# InputBoard_Analog_Digital.net
KiCad netlist of a schematic drawn in Altium Designer
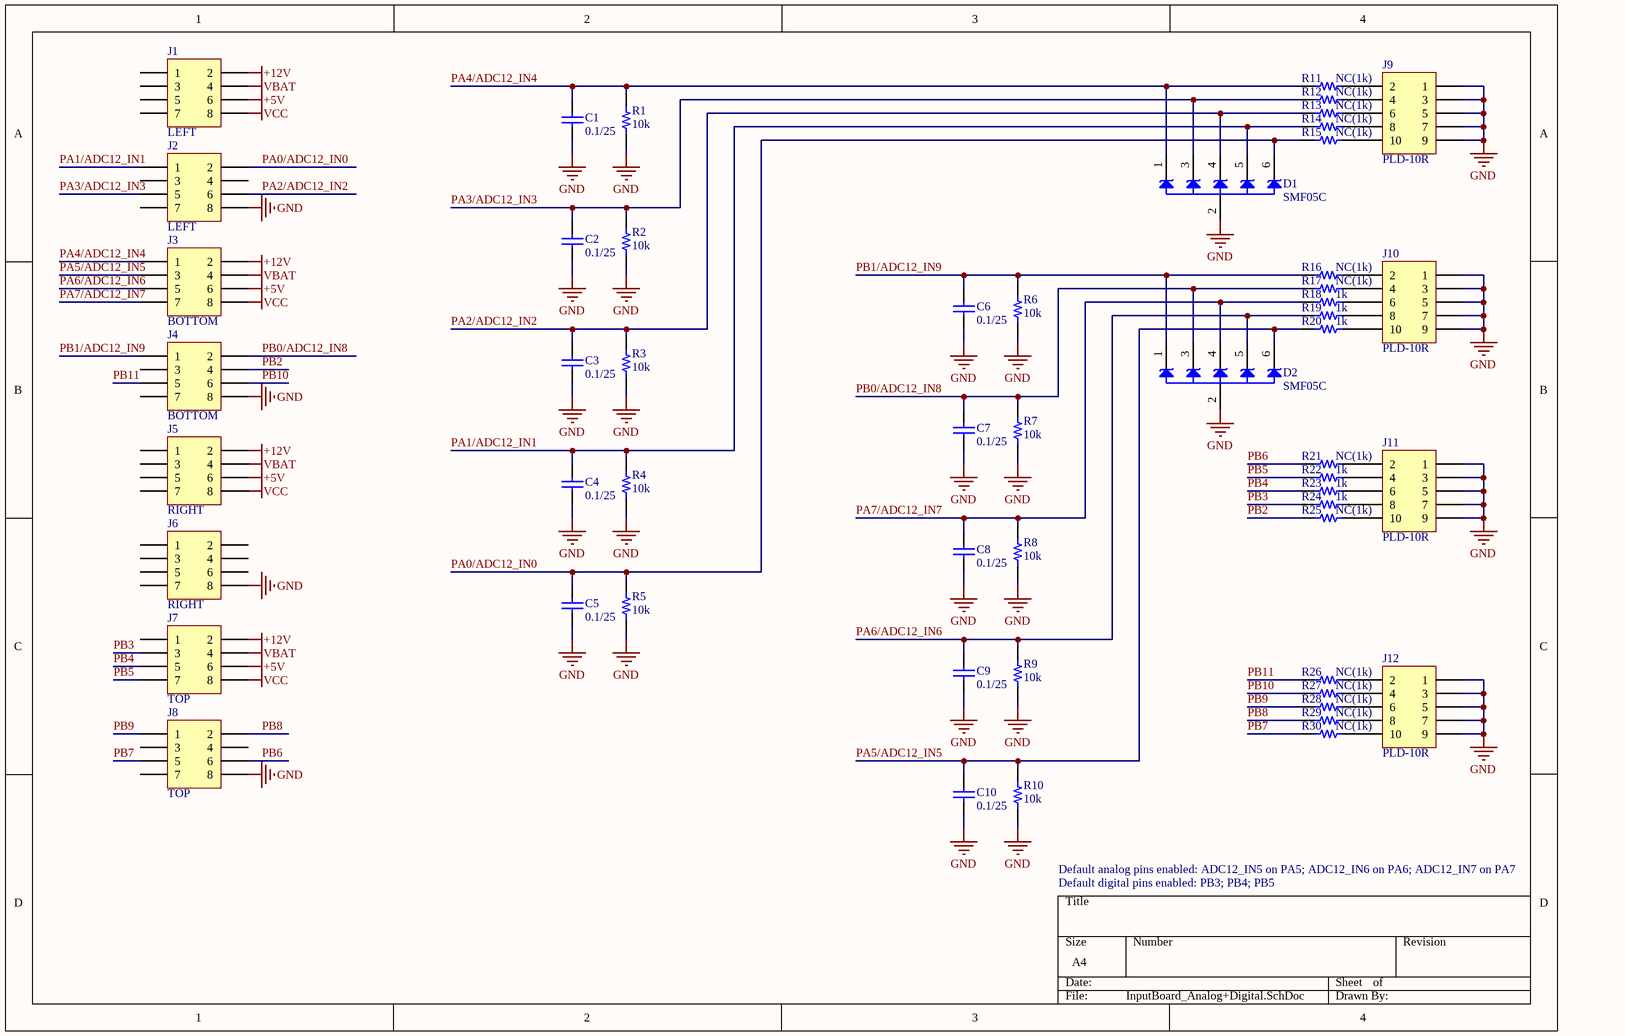
[diagram p0: InputBoard_Analog+Digital.SchDoc]

(export (version "E")
  (design (tool "Eeschema 10.0.6"))
  (components
    (comp (ref "C1")
      (value "0.1/25")
      (footprint "CAP0402")
      (description "Ceramic chip capacitor 0402")
      (fields
        (field (name "PARTNUMBER") "CAP0402")
        (field (name "VOLTAGE") "25")
        (field (name "AUTHOR") "oiezhov")
      )
      (libsource (lib "Library") (part "Capacitor"))
    )
    (comp (ref "C2")
      (value "0.1/25")
      (footprint "CAP0402")
      (description "Ceramic chip capacitor 0402")
      (fields
        (field (name "PARTNUMBER") "CAP0402")
        (field (name "VOLTAGE") "25")
        (field (name "AUTHOR") "oiezhov")
      )
      (libsource (lib "Library") (part "Capacitor"))
    )
    (comp (ref "C3")
      (value "0.1/25")
      (footprint "CAP0402")
      (description "Ceramic chip capacitor 0402")
      (fields
        (field (name "PARTNUMBER") "CAP0402")
        (field (name "VOLTAGE") "25")
        (field (name "AUTHOR") "oiezhov")
      )
      (libsource (lib "Library") (part "Capacitor"))
    )
    (comp (ref "C4")
      (value "0.1/25")
      (footprint "CAP0402")
      (description "Ceramic chip capacitor 0402")
      (fields
        (field (name "PARTNUMBER") "CAP0402")
        (field (name "VOLTAGE") "25")
        (field (name "AUTHOR") "oiezhov")
      )
      (libsource (lib "Library") (part "Capacitor"))
    )
    (comp (ref "C5")
      (value "0.1/25")
      (footprint "CAP0402")
      (description "Ceramic chip capacitor 0402")
      (fields
        (field (name "PARTNUMBER") "CAP0402")
        (field (name "VOLTAGE") "25")
        (field (name "AUTHOR") "oiezhov")
      )
      (libsource (lib "Library") (part "Capacitor"))
    )
    (comp (ref "C6")
      (value "0.1/25")
      (footprint "CAP0402")
      (description "Ceramic chip capacitor 0402")
      (fields
        (field (name "PARTNUMBER") "CAP0402")
        (field (name "VOLTAGE") "25")
        (field (name "AUTHOR") "oiezhov")
      )
      (libsource (lib "Library") (part "Capacitor"))
    )
    (comp (ref "C7")
      (value "0.1/25")
      (footprint "CAP0402")
      (description "Ceramic chip capacitor 0402")
      (fields
        (field (name "PARTNUMBER") "CAP0402")
        (field (name "VOLTAGE") "25")
        (field (name "AUTHOR") "oiezhov")
      )
      (libsource (lib "Library") (part "Capacitor"))
    )
    (comp (ref "C8")
      (value "0.1/25")
      (footprint "CAP0402")
      (description "Ceramic chip capacitor 0402")
      (fields
        (field (name "PARTNUMBER") "CAP0402")
        (field (name "VOLTAGE") "25")
        (field (name "AUTHOR") "oiezhov")
      )
      (libsource (lib "Library") (part "Capacitor"))
    )
    (comp (ref "C9")
      (value "0.1/25")
      (footprint "CAP0402")
      (description "Ceramic chip capacitor 0402")
      (fields
        (field (name "PARTNUMBER") "CAP0402")
        (field (name "VOLTAGE") "25")
        (field (name "AUTHOR") "oiezhov")
      )
      (libsource (lib "Library") (part "Capacitor"))
    )
    (comp (ref "C10")
      (value "0.1/25")
      (footprint "CAP0402")
      (description "Ceramic chip capacitor 0402")
      (fields
        (field (name "PARTNUMBER") "CAP0402")
        (field (name "VOLTAGE") "25")
        (field (name "AUTHOR") "oiezhov")
      )
      (libsource (lib "Library") (part "Capacitor"))
    )
    (comp (ref "D1")
      (value "SMF05C")
      (footprint "SOT363")
      (description "5-line TVS Array for ESD and Latch-Up Protection")
      (fields (field (name "AUTHOR") "oiezhov"))
      (libsource (lib "Library") (part "5x TVS array"))
    )
    (comp (ref "D2")
      (value "SMF05C")
      (footprint "SOT363")
      (description "5-line TVS Array for ESD and Latch-Up Protection")
      (fields (field (name "AUTHOR") "oiezhov"))
      (libsource (lib "Library") (part "5x TVS array"))
    )
    (comp (ref "J1")
      (value "LEFT")
      (footprint "PBDM-8")
      (description "2x4-pin header, pitch 2.54 mm")
      (fields (field (name "PARTNUMBER") "PBDM-8") (field (name "AUTHOR") "oiezhov"))
      (libsource (lib "Library") (part "8-pin dual row connector"))
    )
    (comp (ref "J2")
      (value "LEFT")
      (footprint "PBDM-8")
      (description "2x4-pin header, pitch 2.54 mm")
      (fields (field (name "PARTNUMBER") "PBDM-8") (field (name "AUTHOR") "oiezhov"))
      (libsource (lib "Library") (part "8-pin dual row connector"))
    )
    (comp (ref "J3")
      (value "BOTTOM")
      (footprint "PBDM-8")
      (description "2x4-pin header, pitch 2.54 mm")
      (fields (field (name "PARTNUMBER") "PBDM-8") (field (name "AUTHOR") "oiezhov"))
      (libsource (lib "Library") (part "8-pin dual row connector"))
    )
    (comp (ref "J4")
      (value "BOTTOM")
      (footprint "PBDM-8")
      (description "2x4-pin header, pitch 2.54 mm")
      (fields (field (name "PARTNUMBER") "PBDM-8") (field (name "AUTHOR") "oiezhov"))
      (libsource (lib "Library") (part "8-pin dual row connector"))
    )
    (comp (ref "J5")
      (value "RIGHT")
      (footprint "PBDM-8")
      (description "2x4-pin header, pitch 2.54 mm")
      (fields (field (name "PARTNUMBER") "PBDM-8") (field (name "AUTHOR") "oiezhov"))
      (libsource (lib "Library") (part "8-pin dual row connector"))
    )
    (comp (ref "J6")
      (value "RIGHT")
      (footprint "PBDM-8")
      (description "2x4-pin header, pitch 2.54 mm")
      (fields (field (name "PARTNUMBER") "PBDM-8") (field (name "AUTHOR") "oiezhov"))
      (libsource (lib "Library") (part "8-pin dual row connector"))
    )
    (comp (ref "J7")
      (value "TOP")
      (footprint "PBDM-8")
      (description "2x4-pin header, pitch 2.54 mm")
      (fields (field (name "PARTNUMBER") "PBDM-8") (field (name "AUTHOR") "oiezhov"))
      (libsource (lib "Library") (part "8-pin dual row connector"))
    )
    (comp (ref "J8")
      (value "TOP")
      (footprint "PBDM-8")
      (description "2x4-pin header, pitch 2.54 mm")
      (fields (field (name "PARTNUMBER") "PBDM-8") (field (name "AUTHOR") "oiezhov"))
      (libsource (lib "Library") (part "8-pin dual row connector"))
    )
    (comp (ref "J9")
      (value "PLD-10R")
      (footprint "PLD-10R")
      (description "2x5-pin angle header, pitch 2.54 mm")
      (fields (field (name "AUTHOR") "oiezhov"))
      (libsource (lib "Library") (part "10-pin dual row connector"))
    )
    (comp (ref "J10")
      (value "PLD-10R")
      (footprint "PLD-10R")
      (description "2x5-pin angle header, pitch 2.54 mm")
      (fields (field (name "AUTHOR") "oiezhov"))
      (libsource (lib "Library") (part "10-pin dual row connector"))
    )
    (comp (ref "J11")
      (value "PLD-10R")
      (footprint "PLD-10R")
      (description "2x5-pin angle header, pitch 2.54 mm")
      (fields (field (name "AUTHOR") "oiezhov"))
      (libsource (lib "Library") (part "10-pin dual row connector"))
    )
    (comp (ref "J12")
      (value "PLD-10R")
      (footprint "PLD-10R")
      (description "2x5-pin angle header, pitch 2.54 mm")
      (fields (field (name "AUTHOR") "oiezhov"))
      (libsource (lib "Library") (part "10-pin dual row connector"))
    )
    (comp (ref "R1")
      (value "10k")
      (footprint "RES0402")
      (description "Ceramic chip resistor")
      (fields (field (name "PARTNUMBER") "RES0402") (field (name "AUTHOR") "oiezhov"))
      (libsource (lib "Library") (part "Resistor"))
    )
    (comp (ref "R2")
      (value "10k")
      (footprint "RES0402")
      (description "Ceramic chip resistor")
      (fields (field (name "PARTNUMBER") "RES0402") (field (name "AUTHOR") "oiezhov"))
      (libsource (lib "Library") (part "Resistor"))
    )
    (comp (ref "R3")
      (value "10k")
      (footprint "RES0402")
      (description "Ceramic chip resistor")
      (fields (field (name "PARTNUMBER") "RES0402") (field (name "AUTHOR") "oiezhov"))
      (libsource (lib "Library") (part "Resistor"))
    )
    (comp (ref "R4")
      (value "10k")
      (footprint "RES0402")
      (description "Ceramic chip resistor")
      (fields (field (name "PARTNUMBER") "RES0402") (field (name "AUTHOR") "oiezhov"))
      (libsource (lib "Library") (part "Resistor"))
    )
    (comp (ref "R5")
      (value "10k")
      (footprint "RES0402")
      (description "Ceramic chip resistor")
      (fields (field (name "PARTNUMBER") "RES0402") (field (name "AUTHOR") "oiezhov"))
      (libsource (lib "Library") (part "Resistor"))
    )
    (comp (ref "R6")
      (value "10k")
      (footprint "RES0402")
      (description "Ceramic chip resistor")
      (fields (field (name "PARTNUMBER") "RES0402") (field (name "AUTHOR") "oiezhov"))
      (libsource (lib "Library") (part "Resistor"))
    )
    (comp (ref "R7")
      (value "10k")
      (footprint "RES0402")
      (description "Ceramic chip resistor")
      (fields (field (name "PARTNUMBER") "RES0402") (field (name "AUTHOR") "oiezhov"))
      (libsource (lib "Library") (part "Resistor"))
    )
    (comp (ref "R8")
      (value "10k")
      (footprint "RES0402")
      (description "Ceramic chip resistor")
      (fields (field (name "PARTNUMBER") "RES0402") (field (name "AUTHOR") "oiezhov"))
      (libsource (lib "Library") (part "Resistor"))
    )
    (comp (ref "R9")
      (value "10k")
      (footprint "RES0402")
      (description "Ceramic chip resistor")
      (fields (field (name "PARTNUMBER") "RES0402") (field (name "AUTHOR") "oiezhov"))
      (libsource (lib "Library") (part "Resistor"))
    )
    (comp (ref "R10")
      (value "10k")
      (footprint "RES0402")
      (description "Ceramic chip resistor")
      (fields (field (name "PARTNUMBER") "RES0402") (field (name "AUTHOR") "oiezhov"))
      (libsource (lib "Library") (part "Resistor"))
    )
    (comp (ref "R11")
      (value "NC(1k)")
      (footprint "RES0402")
      (description "Ceramic chip resistor")
      (fields (field (name "PARTNUMBER") "RES0402") (field (name "AUTHOR") "oiezhov"))
      (libsource (lib "Library") (part "Resistor"))
    )
    (comp (ref "R12")
      (value "NC(1k)")
      (footprint "RES0402")
      (description "Ceramic chip resistor")
      (fields (field (name "PARTNUMBER") "RES0402") (field (name "AUTHOR") "oiezhov"))
      (libsource (lib "Library") (part "Resistor"))
    )
    (comp (ref "R13")
      (value "NC(1k)")
      (footprint "RES0402")
      (description "Ceramic chip resistor")
      (fields (field (name "PARTNUMBER") "RES0402") (field (name "AUTHOR") "oiezhov"))
      (libsource (lib "Library") (part "Resistor"))
    )
    (comp (ref "R14")
      (value "NC(1k)")
      (footprint "RES0402")
      (description "Ceramic chip resistor")
      (fields (field (name "PARTNUMBER") "RES0402") (field (name "AUTHOR") "oiezhov"))
      (libsource (lib "Library") (part "Resistor"))
    )
    (comp (ref "R15")
      (value "NC(1k)")
      (footprint "RES0402")
      (description "Ceramic chip resistor")
      (fields (field (name "PARTNUMBER") "RES0402") (field (name "AUTHOR") "oiezhov"))
      (libsource (lib "Library") (part "Resistor"))
    )
    (comp (ref "R16")
      (value "NC(1k)")
      (footprint "RES0402")
      (description "Ceramic chip resistor")
      (fields (field (name "PARTNUMBER") "RES0402") (field (name "AUTHOR") "oiezhov"))
      (libsource (lib "Library") (part "Resistor"))
    )
    (comp (ref "R17")
      (value "NC(1k)")
      (footprint "RES0402")
      (description "Ceramic chip resistor")
      (fields (field (name "PARTNUMBER") "RES0402") (field (name "AUTHOR") "oiezhov"))
      (libsource (lib "Library") (part "Resistor"))
    )
    (comp (ref "R18")
      (value "1k")
      (footprint "RES0402")
      (description "Ceramic chip resistor")
      (fields (field (name "PARTNUMBER") "RES0402") (field (name "AUTHOR") "oiezhov"))
      (libsource (lib "Library") (part "Resistor"))
    )
    (comp (ref "R19")
      (value "1k")
      (footprint "RES0402")
      (description "Ceramic chip resistor")
      (fields (field (name "PARTNUMBER") "RES0402") (field (name "AUTHOR") "oiezhov"))
      (libsource (lib "Library") (part "Resistor"))
    )
    (comp (ref "R20")
      (value "1k")
      (footprint "RES0402")
      (description "Ceramic chip resistor")
      (fields (field (name "PARTNUMBER") "RES0402") (field (name "AUTHOR") "oiezhov"))
      (libsource (lib "Library") (part "Resistor"))
    )
    (comp (ref "R21")
      (value "NC(1k)")
      (footprint "RES0402")
      (description "Ceramic chip resistor")
      (fields (field (name "PARTNUMBER") "RES0402") (field (name "AUTHOR") "oiezhov"))
      (libsource (lib "Library") (part "Resistor"))
    )
    (comp (ref "R22")
      (value "1k")
      (footprint "RES0402")
      (description "Ceramic chip resistor")
      (fields (field (name "PARTNUMBER") "RES0402") (field (name "AUTHOR") "oiezhov"))
      (libsource (lib "Library") (part "Resistor"))
    )
    (comp (ref "R23")
      (value "1k")
      (footprint "RES0402")
      (description "Ceramic chip resistor")
      (fields (field (name "PARTNUMBER") "RES0402") (field (name "AUTHOR") "oiezhov"))
      (libsource (lib "Library") (part "Resistor"))
    )
    (comp (ref "R24")
      (value "1k")
      (footprint "RES0402")
      (description "Ceramic chip resistor")
      (fields (field (name "PARTNUMBER") "RES0402") (field (name "AUTHOR") "oiezhov"))
      (libsource (lib "Library") (part "Resistor"))
    )
    (comp (ref "R25")
      (value "NC(1k)")
      (footprint "RES0402")
      (description "Ceramic chip resistor")
      (fields (field (name "PARTNUMBER") "RES0402") (field (name "AUTHOR") "oiezhov"))
      (libsource (lib "Library") (part "Resistor"))
    )
    (comp (ref "R26")
      (value "NC(1k)")
      (footprint "RES0402")
      (description "Ceramic chip resistor")
      (fields (field (name "PARTNUMBER") "RES0402") (field (name "AUTHOR") "oiezhov"))
      (libsource (lib "Library") (part "Resistor"))
    )
    (comp (ref "R27")
      (value "NC(1k)")
      (footprint "RES0402")
      (description "Ceramic chip resistor")
      (fields (field (name "PARTNUMBER") "RES0402") (field (name "AUTHOR") "oiezhov"))
      (libsource (lib "Library") (part "Resistor"))
    )
    (comp (ref "R28")
      (value "NC(1k)")
      (footprint "RES0402")
      (description "Ceramic chip resistor")
      (fields (field (name "PARTNUMBER") "RES0402") (field (name "AUTHOR") "oiezhov"))
      (libsource (lib "Library") (part "Resistor"))
    )
    (comp (ref "R29")
      (value "NC(1k)")
      (footprint "RES0402")
      (description "Ceramic chip resistor")
      (fields (field (name "PARTNUMBER") "RES0402") (field (name "AUTHOR") "oiezhov"))
      (libsource (lib "Library") (part "Resistor"))
    )
    (comp (ref "R30")
      (value "NC(1k)")
      (footprint "RES0402")
      (description "Ceramic chip resistor")
      (fields (field (name "PARTNUMBER") "RES0402") (field (name "AUTHOR") "oiezhov"))
      (libsource (lib "Library") (part "Resistor"))
    )
  )
  (nets
    (net (code "1") (name "+5V") (class "Default")
      (node (ref "J1") (pin "6") (pinfunction "6_6") (pintype "passive"))
      (node (ref "J3") (pin "6") (pinfunction "6_6") (pintype "passive"))
      (node (ref "J5") (pin "6") (pinfunction "6_6") (pintype "passive"))
      (node (ref "J7") (pin "6") (pinfunction "6_6") (pintype "passive"))
    )
    (net (code "2") (name "+12V") (class "Default")
      (node (ref "J1") (pin "2") (pinfunction "2_2") (pintype "passive"))
      (node (ref "J3") (pin "2") (pinfunction "2_2") (pintype "passive"))
      (node (ref "J5") (pin "2") (pinfunction "2_2") (pintype "passive"))
      (node (ref "J7") (pin "2") (pinfunction "2_2") (pintype "passive"))
    )
    (net (code "3") (name "/PA0{slash}ADC12_IN0") (class "Default")
      (node (ref "C5") (pin "2") (pinfunction "2_2") (pintype "passive"))
      (node (ref "D1") (pin "6") (pinfunction "6_6") (pintype "passive"))
      (node (ref "J2") (pin "2") (pinfunction "2_2") (pintype "passive"))
      (node (ref "R15") (pin "1") (pinfunction "1_1") (pintype "passive"))
      (node (ref "R5") (pin "1") (pinfunction "1_1") (pintype "passive"))
    )
    (net (code "4") (name "/PA1{slash}ADC12_IN1") (class "Default")
      (node (ref "C4") (pin "2") (pinfunction "2_2") (pintype "passive"))
      (node (ref "D1") (pin "5") (pinfunction "5_5") (pintype "passive"))
      (node (ref "J2") (pin "1") (pinfunction "1_1") (pintype "passive"))
      (node (ref "R14") (pin "1") (pinfunction "1_1") (pintype "passive"))
      (node (ref "R4") (pin "1") (pinfunction "1_1") (pintype "passive"))
    )
    (net (code "5") (name "/PA2{slash}ADC12_IN2") (class "Default")
      (node (ref "C3") (pin "2") (pinfunction "2_2") (pintype "passive"))
      (node (ref "D1") (pin "4") (pinfunction "4_4") (pintype "passive"))
      (node (ref "J2") (pin "6") (pinfunction "6_6") (pintype "passive"))
      (node (ref "R13") (pin "1") (pinfunction "1_1") (pintype "passive"))
      (node (ref "R3") (pin "1") (pinfunction "1_1") (pintype "passive"))
    )
    (net (code "6") (name "/PA3{slash}ADC12_IN3") (class "Default")
      (node (ref "C2") (pin "2") (pinfunction "2_2") (pintype "passive"))
      (node (ref "D1") (pin "3") (pinfunction "3_3") (pintype "passive"))
      (node (ref "J2") (pin "5") (pinfunction "5_5") (pintype "passive"))
      (node (ref "R12") (pin "1") (pinfunction "1_1") (pintype "passive"))
      (node (ref "R2") (pin "1") (pinfunction "1_1") (pintype "passive"))
    )
    (net (code "7") (name "/PA4{slash}ADC12_IN4") (class "Default")
      (node (ref "C1") (pin "2") (pinfunction "2_2") (pintype "passive"))
      (node (ref "D1") (pin "1") (pinfunction "1_1") (pintype "passive"))
      (node (ref "J3") (pin "1") (pinfunction "1_1") (pintype "passive"))
      (node (ref "R1") (pin "1") (pinfunction "1_1") (pintype "passive"))
      (node (ref "R11") (pin "1") (pinfunction "1_1") (pintype "passive"))
    )
    (net (code "8") (name "/PA5{slash}ADC12_IN5") (class "Default")
      (node (ref "C10") (pin "2") (pinfunction "2_2") (pintype "passive"))
      (node (ref "D2") (pin "6") (pinfunction "6_6") (pintype "passive"))
      (node (ref "J3") (pin "3") (pinfunction "3_3") (pintype "passive"))
      (node (ref "R10") (pin "1") (pinfunction "1_1") (pintype "passive"))
      (node (ref "R20") (pin "1") (pinfunction "1_1") (pintype "passive"))
    )
    (net (code "9") (name "/PA6{slash}ADC12_IN6") (class "Default")
      (node (ref "C9") (pin "2") (pinfunction "2_2") (pintype "passive"))
      (node (ref "D2") (pin "5") (pinfunction "5_5") (pintype "passive"))
      (node (ref "J3") (pin "5") (pinfunction "5_5") (pintype "passive"))
      (node (ref "R19") (pin "1") (pinfunction "1_1") (pintype "passive"))
      (node (ref "R9") (pin "1") (pinfunction "1_1") (pintype "passive"))
    )
    (net (code "10") (name "/PA7{slash}ADC12_IN7") (class "Default")
      (node (ref "C8") (pin "2") (pinfunction "2_2") (pintype "passive"))
      (node (ref "D2") (pin "4") (pinfunction "4_4") (pintype "passive"))
      (node (ref "J3") (pin "7") (pinfunction "7_7") (pintype "passive"))
      (node (ref "R18") (pin "1") (pinfunction "1_1") (pintype "passive"))
      (node (ref "R8") (pin "1") (pinfunction "1_1") (pintype "passive"))
    )
    (net (code "11") (name "/PB0{slash}ADC12_IN8") (class "Default")
      (node (ref "C7") (pin "2") (pinfunction "2_2") (pintype "passive"))
      (node (ref "D2") (pin "3") (pinfunction "3_3") (pintype "passive"))
      (node (ref "J4") (pin "2") (pinfunction "2_2") (pintype "passive"))
      (node (ref "R17") (pin "1") (pinfunction "1_1") (pintype "passive"))
      (node (ref "R7") (pin "1") (pinfunction "1_1") (pintype "passive"))
    )
    (net (code "12") (name "/PB1{slash}ADC12_IN9") (class "Default")
      (node (ref "C6") (pin "2") (pinfunction "2_2") (pintype "passive"))
      (node (ref "D2") (pin "1") (pinfunction "1_1") (pintype "passive"))
      (node (ref "J4") (pin "1") (pinfunction "1_1") (pintype "passive"))
      (node (ref "R16") (pin "1") (pinfunction "1_1") (pintype "passive"))
      (node (ref "R6") (pin "1") (pinfunction "1_1") (pintype "passive"))
    )
    (net (code "13") (name "/PB2") (class "Default")
      (node (ref "J4") (pin "4") (pinfunction "4_4") (pintype "passive"))
      (node (ref "R25") (pin "1") (pinfunction "1_1") (pintype "passive"))
    )
    (net (code "14") (name "/PB3") (class "Default")
      (node (ref "J7") (pin "3") (pinfunction "3_3") (pintype "passive"))
      (node (ref "R24") (pin "1") (pinfunction "1_1") (pintype "passive"))
    )
    (net (code "15") (name "/PB4") (class "Default")
      (node (ref "J7") (pin "5") (pinfunction "5_5") (pintype "passive"))
      (node (ref "R23") (pin "1") (pinfunction "1_1") (pintype "passive"))
    )
    (net (code "16") (name "/PB5") (class "Default")
      (node (ref "J7") (pin "7") (pinfunction "7_7") (pintype "passive"))
      (node (ref "R22") (pin "1") (pinfunction "1_1") (pintype "passive"))
    )
    (net (code "17") (name "/PB6") (class "Default")
      (node (ref "J8") (pin "6") (pinfunction "6_6") (pintype "passive"))
      (node (ref "R21") (pin "1") (pinfunction "1_1") (pintype "passive"))
    )
    (net (code "18") (name "/PB7") (class "Default")
      (node (ref "J8") (pin "5") (pinfunction "5_5") (pintype "passive"))
      (node (ref "R30") (pin "1") (pinfunction "1_1") (pintype "passive"))
    )
    (net (code "19") (name "/PB8") (class "Default")
      (node (ref "J8") (pin "2") (pinfunction "2_2") (pintype "passive"))
      (node (ref "R29") (pin "1") (pinfunction "1_1") (pintype "passive"))
    )
    (net (code "20") (name "/PB9") (class "Default")
      (node (ref "J8") (pin "1") (pinfunction "1_1") (pintype "passive"))
      (node (ref "R28") (pin "1") (pinfunction "1_1") (pintype "passive"))
    )
    (net (code "21") (name "/PB10") (class "Default")
      (node (ref "J4") (pin "6") (pinfunction "6_6") (pintype "passive"))
      (node (ref "R27") (pin "1") (pinfunction "1_1") (pintype "passive"))
    )
    (net (code "22") (name "/PB11") (class "Default")
      (node (ref "J4") (pin "5") (pinfunction "5_5") (pintype "passive"))
      (node (ref "R26") (pin "1") (pinfunction "1_1") (pintype "passive"))
    )
    (net (code "23") (name "GND") (class "Default")
      (node (ref "C1") (pin "1") (pinfunction "1_1") (pintype "passive"))
      (node (ref "C10") (pin "1") (pinfunction "1_1") (pintype "passive"))
      (node (ref "C2") (pin "1") (pinfunction "1_1") (pintype "passive"))
      (node (ref "C3") (pin "1") (pinfunction "1_1") (pintype "passive"))
      (node (ref "C4") (pin "1") (pinfunction "1_1") (pintype "passive"))
      (node (ref "C5") (pin "1") (pinfunction "1_1") (pintype "passive"))
      (node (ref "C6") (pin "1") (pinfunction "1_1") (pintype "passive"))
      (node (ref "C7") (pin "1") (pinfunction "1_1") (pintype "passive"))
      (node (ref "C8") (pin "1") (pinfunction "1_1") (pintype "passive"))
      (node (ref "C9") (pin "1") (pinfunction "1_1") (pintype "passive"))
      (node (ref "D1") (pin "2") (pinfunction "2_2") (pintype "passive"))
      (node (ref "D2") (pin "2") (pinfunction "2_2") (pintype "passive"))
      (node (ref "J10") (pin "1") (pinfunction "1_1") (pintype "passive"))
      (node (ref "J10") (pin "3") (pinfunction "3_3") (pintype "passive"))
      (node (ref "J10") (pin "5") (pinfunction "5_5") (pintype "passive"))
      (node (ref "J10") (pin "7") (pinfunction "7_7") (pintype "passive"))
      (node (ref "J10") (pin "9") (pinfunction "9_9") (pintype "passive"))
      (node (ref "J11") (pin "1") (pinfunction "1_1") (pintype "passive"))
      (node (ref "J11") (pin "3") (pinfunction "3_3") (pintype "passive"))
      (node (ref "J11") (pin "5") (pinfunction "5_5") (pintype "passive"))
      (node (ref "J11") (pin "7") (pinfunction "7_7") (pintype "passive"))
      (node (ref "J11") (pin "9") (pinfunction "9_9") (pintype "passive"))
      (node (ref "J12") (pin "1") (pinfunction "1_1") (pintype "passive"))
      (node (ref "J12") (pin "3") (pinfunction "3_3") (pintype "passive"))
      (node (ref "J12") (pin "5") (pinfunction "5_5") (pintype "passive"))
      (node (ref "J12") (pin "7") (pinfunction "7_7") (pintype "passive"))
      (node (ref "J12") (pin "9") (pinfunction "9_9") (pintype "passive"))
      (node (ref "J2") (pin "8") (pinfunction "8_8") (pintype "passive"))
      (node (ref "J4") (pin "8") (pinfunction "8_8") (pintype "passive"))
      (node (ref "J6") (pin "8") (pinfunction "8_8") (pintype "passive"))
      (node (ref "J8") (pin "8") (pinfunction "8_8") (pintype "passive"))
      (node (ref "J9") (pin "1") (pinfunction "1_1") (pintype "passive"))
      (node (ref "J9") (pin "3") (pinfunction "3_3") (pintype "passive"))
      (node (ref "J9") (pin "5") (pinfunction "5_5") (pintype "passive"))
      (node (ref "J9") (pin "7") (pinfunction "7_7") (pintype "passive"))
      (node (ref "J9") (pin "9") (pinfunction "9_9") (pintype "passive"))
      (node (ref "R1") (pin "2") (pinfunction "2_2") (pintype "passive"))
      (node (ref "R10") (pin "2") (pinfunction "2_2") (pintype "passive"))
      (node (ref "R2") (pin "2") (pinfunction "2_2") (pintype "passive"))
      (node (ref "R3") (pin "2") (pinfunction "2_2") (pintype "passive"))
      (node (ref "R4") (pin "2") (pinfunction "2_2") (pintype "passive"))
      (node (ref "R5") (pin "2") (pinfunction "2_2") (pintype "passive"))
      (node (ref "R6") (pin "2") (pinfunction "2_2") (pintype "passive"))
      (node (ref "R7") (pin "2") (pinfunction "2_2") (pintype "passive"))
      (node (ref "R8") (pin "2") (pinfunction "2_2") (pintype "passive"))
      (node (ref "R9") (pin "2") (pinfunction "2_2") (pintype "passive"))
    )
    (net (code "24") (name "Net-(J9-Pad2)") (class "Default")
      (node (ref "J9") (pin "2") (pinfunction "2_2") (pintype "passive"))
      (node (ref "R11") (pin "2") (pinfunction "2_2") (pintype "passive"))
    )
    (net (code "25") (name "Net-(J9-Pad4)") (class "Default")
      (node (ref "J9") (pin "4") (pinfunction "4_4") (pintype "passive"))
      (node (ref "R12") (pin "2") (pinfunction "2_2") (pintype "passive"))
    )
    (net (code "26") (name "Net-(J9-Pad6)") (class "Default")
      (node (ref "J9") (pin "6") (pinfunction "6_6") (pintype "passive"))
      (node (ref "R13") (pin "2") (pinfunction "2_2") (pintype "passive"))
    )
    (net (code "27") (name "Net-(J9-Pad8)") (class "Default")
      (node (ref "J9") (pin "8") (pinfunction "8_8") (pintype "passive"))
      (node (ref "R14") (pin "2") (pinfunction "2_2") (pintype "passive"))
    )
    (net (code "28") (name "Net-(J9-Pad10)") (class "Default")
      (node (ref "J9") (pin "10") (pinfunction "10_10") (pintype "passive"))
      (node (ref "R15") (pin "2") (pinfunction "2_2") (pintype "passive"))
    )
    (net (code "29") (name "Net-(J10-Pad2)") (class "Default")
      (node (ref "J10") (pin "2") (pinfunction "2_2") (pintype "passive"))
      (node (ref "R16") (pin "2") (pinfunction "2_2") (pintype "passive"))
    )
    (net (code "30") (name "Net-(J10-Pad4)") (class "Default")
      (node (ref "J10") (pin "4") (pinfunction "4_4") (pintype "passive"))
      (node (ref "R17") (pin "2") (pinfunction "2_2") (pintype "passive"))
    )
    (net (code "31") (name "Net-(J10-Pad6)") (class "Default")
      (node (ref "J10") (pin "6") (pinfunction "6_6") (pintype "passive"))
      (node (ref "R18") (pin "2") (pinfunction "2_2") (pintype "passive"))
    )
    (net (code "32") (name "Net-(J10-Pad8)") (class "Default")
      (node (ref "J10") (pin "8") (pinfunction "8_8") (pintype "passive"))
      (node (ref "R19") (pin "2") (pinfunction "2_2") (pintype "passive"))
    )
    (net (code "33") (name "Net-(J10-Pad10)") (class "Default")
      (node (ref "J10") (pin "10") (pinfunction "10_10") (pintype "passive"))
      (node (ref "R20") (pin "2") (pinfunction "2_2") (pintype "passive"))
    )
    (net (code "34") (name "Net-(J11-Pad2)") (class "Default")
      (node (ref "J11") (pin "2") (pinfunction "2_2") (pintype "passive"))
      (node (ref "R21") (pin "2") (pinfunction "2_2") (pintype "passive"))
    )
    (net (code "35") (name "Net-(J11-Pad4)") (class "Default")
      (node (ref "J11") (pin "4") (pinfunction "4_4") (pintype "passive"))
      (node (ref "R22") (pin "2") (pinfunction "2_2") (pintype "passive"))
    )
    (net (code "36") (name "Net-(J11-Pad6)") (class "Default")
      (node (ref "J11") (pin "6") (pinfunction "6_6") (pintype "passive"))
      (node (ref "R23") (pin "2") (pinfunction "2_2") (pintype "passive"))
    )
    (net (code "37") (name "Net-(J11-Pad8)") (class "Default")
      (node (ref "J11") (pin "8") (pinfunction "8_8") (pintype "passive"))
      (node (ref "R24") (pin "2") (pinfunction "2_2") (pintype "passive"))
    )
    (net (code "38") (name "Net-(J11-Pad10)") (class "Default")
      (node (ref "J11") (pin "10") (pinfunction "10_10") (pintype "passive"))
      (node (ref "R25") (pin "2") (pinfunction "2_2") (pintype "passive"))
    )
    (net (code "39") (name "Net-(J12-Pad2)") (class "Default")
      (node (ref "J12") (pin "2") (pinfunction "2_2") (pintype "passive"))
      (node (ref "R26") (pin "2") (pinfunction "2_2") (pintype "passive"))
    )
    (net (code "40") (name "Net-(J12-Pad4)") (class "Default")
      (node (ref "J12") (pin "4") (pinfunction "4_4") (pintype "passive"))
      (node (ref "R27") (pin "2") (pinfunction "2_2") (pintype "passive"))
    )
    (net (code "41") (name "Net-(J12-Pad6)") (class "Default")
      (node (ref "J12") (pin "6") (pinfunction "6_6") (pintype "passive"))
      (node (ref "R28") (pin "2") (pinfunction "2_2") (pintype "passive"))
    )
    (net (code "42") (name "Net-(J12-Pad8)") (class "Default")
      (node (ref "J12") (pin "8") (pinfunction "8_8") (pintype "passive"))
      (node (ref "R29") (pin "2") (pinfunction "2_2") (pintype "passive"))
    )
    (net (code "43") (name "Net-(J12-Pad10)") (class "Default")
      (node (ref "J12") (pin "10") (pinfunction "10_10") (pintype "passive"))
      (node (ref "R30") (pin "2") (pinfunction "2_2") (pintype "passive"))
    )
    (net (code "44") (name "VBAT") (class "Default")
      (node (ref "J1") (pin "4") (pinfunction "4_4") (pintype "passive"))
      (node (ref "J3") (pin "4") (pinfunction "4_4") (pintype "passive"))
      (node (ref "J5") (pin "4") (pinfunction "4_4") (pintype "passive"))
      (node (ref "J7") (pin "4") (pinfunction "4_4") (pintype "passive"))
    )
    (net (code "45") (name "VCC") (class "Default")
      (node (ref "J1") (pin "8") (pinfunction "8_8") (pintype "passive"))
      (node (ref "J3") (pin "8") (pinfunction "8_8") (pintype "passive"))
      (node (ref "J5") (pin "8") (pinfunction "8_8") (pintype "passive"))
      (node (ref "J7") (pin "8") (pinfunction "8_8") (pintype "passive"))
    )
    (net (code "46") (name "unconnected-(J1-Pad1)") (class "Default")
      (node (ref "J1") (pin "1") (pinfunction "1_1") (pintype "passive"))
    )
    (net (code "47") (name "unconnected-(J1-Pad3)") (class "Default")
      (node (ref "J1") (pin "3") (pinfunction "3_3") (pintype "passive"))
    )
    (net (code "48") (name "unconnected-(J1-Pad5)") (class "Default")
      (node (ref "J1") (pin "5") (pinfunction "5_5") (pintype "passive"))
    )
    (net (code "49") (name "unconnected-(J1-Pad7)") (class "Default")
      (node (ref "J1") (pin "7") (pinfunction "7_7") (pintype "passive"))
    )
    (net (code "50") (name "unconnected-(J2-Pad3)") (class "Default")
      (node (ref "J2") (pin "3") (pinfunction "3_3") (pintype "passive"))
    )
    (net (code "51") (name "unconnected-(J2-Pad4)") (class "Default")
      (node (ref "J2") (pin "4") (pinfunction "4_4") (pintype "passive"))
    )
    (net (code "52") (name "unconnected-(J2-Pad7)") (class "Default")
      (node (ref "J2") (pin "7") (pinfunction "7_7") (pintype "passive"))
    )
    (net (code "53") (name "unconnected-(J4-Pad3)") (class "Default")
      (node (ref "J4") (pin "3") (pinfunction "3_3") (pintype "passive"))
    )
    (net (code "54") (name "unconnected-(J4-Pad7)") (class "Default")
      (node (ref "J4") (pin "7") (pinfunction "7_7") (pintype "passive"))
    )
    (net (code "55") (name "unconnected-(J5-Pad1)") (class "Default")
      (node (ref "J5") (pin "1") (pinfunction "1_1") (pintype "passive"))
    )
    (net (code "56") (name "unconnected-(J5-Pad3)") (class "Default")
      (node (ref "J5") (pin "3") (pinfunction "3_3") (pintype "passive"))
    )
    (net (code "57") (name "unconnected-(J5-Pad5)") (class "Default")
      (node (ref "J5") (pin "5") (pinfunction "5_5") (pintype "passive"))
    )
    (net (code "58") (name "unconnected-(J5-Pad7)") (class "Default")
      (node (ref "J5") (pin "7") (pinfunction "7_7") (pintype "passive"))
    )
    (net (code "59") (name "unconnected-(J6-Pad1)") (class "Default")
      (node (ref "J6") (pin "1") (pinfunction "1_1") (pintype "passive"))
    )
    (net (code "60") (name "unconnected-(J6-Pad2)") (class "Default")
      (node (ref "J6") (pin "2") (pinfunction "2_2") (pintype "passive"))
    )
    (net (code "61") (name "unconnected-(J6-Pad3)") (class "Default")
      (node (ref "J6") (pin "3") (pinfunction "3_3") (pintype "passive"))
    )
    (net (code "62") (name "unconnected-(J6-Pad4)") (class "Default")
      (node (ref "J6") (pin "4") (pinfunction "4_4") (pintype "passive"))
    )
    (net (code "63") (name "unconnected-(J6-Pad5)") (class "Default")
      (node (ref "J6") (pin "5") (pinfunction "5_5") (pintype "passive"))
    )
    (net (code "64") (name "unconnected-(J6-Pad6)") (class "Default")
      (node (ref "J6") (pin "6") (pinfunction "6_6") (pintype "passive"))
    )
    (net (code "65") (name "unconnected-(J6-Pad7)") (class "Default")
      (node (ref "J6") (pin "7") (pinfunction "7_7") (pintype "passive"))
    )
    (net (code "66") (name "unconnected-(J7-Pad1)") (class "Default")
      (node (ref "J7") (pin "1") (pinfunction "1_1") (pintype "passive"))
    )
    (net (code "67") (name "unconnected-(J8-Pad3)") (class "Default")
      (node (ref "J8") (pin "3") (pinfunction "3_3") (pintype "passive"))
    )
    (net (code "68") (name "unconnected-(J8-Pad4)") (class "Default")
      (node (ref "J8") (pin "4") (pinfunction "4_4") (pintype "passive"))
    )
    (net (code "69") (name "unconnected-(J8-Pad7)") (class "Default")
      (node (ref "J8") (pin "7") (pinfunction "7_7") (pintype "passive"))
    )
  )
)
